# Microcontroller_CC1350.net
KiCad netlist of a schematic drawn in Altium Designer
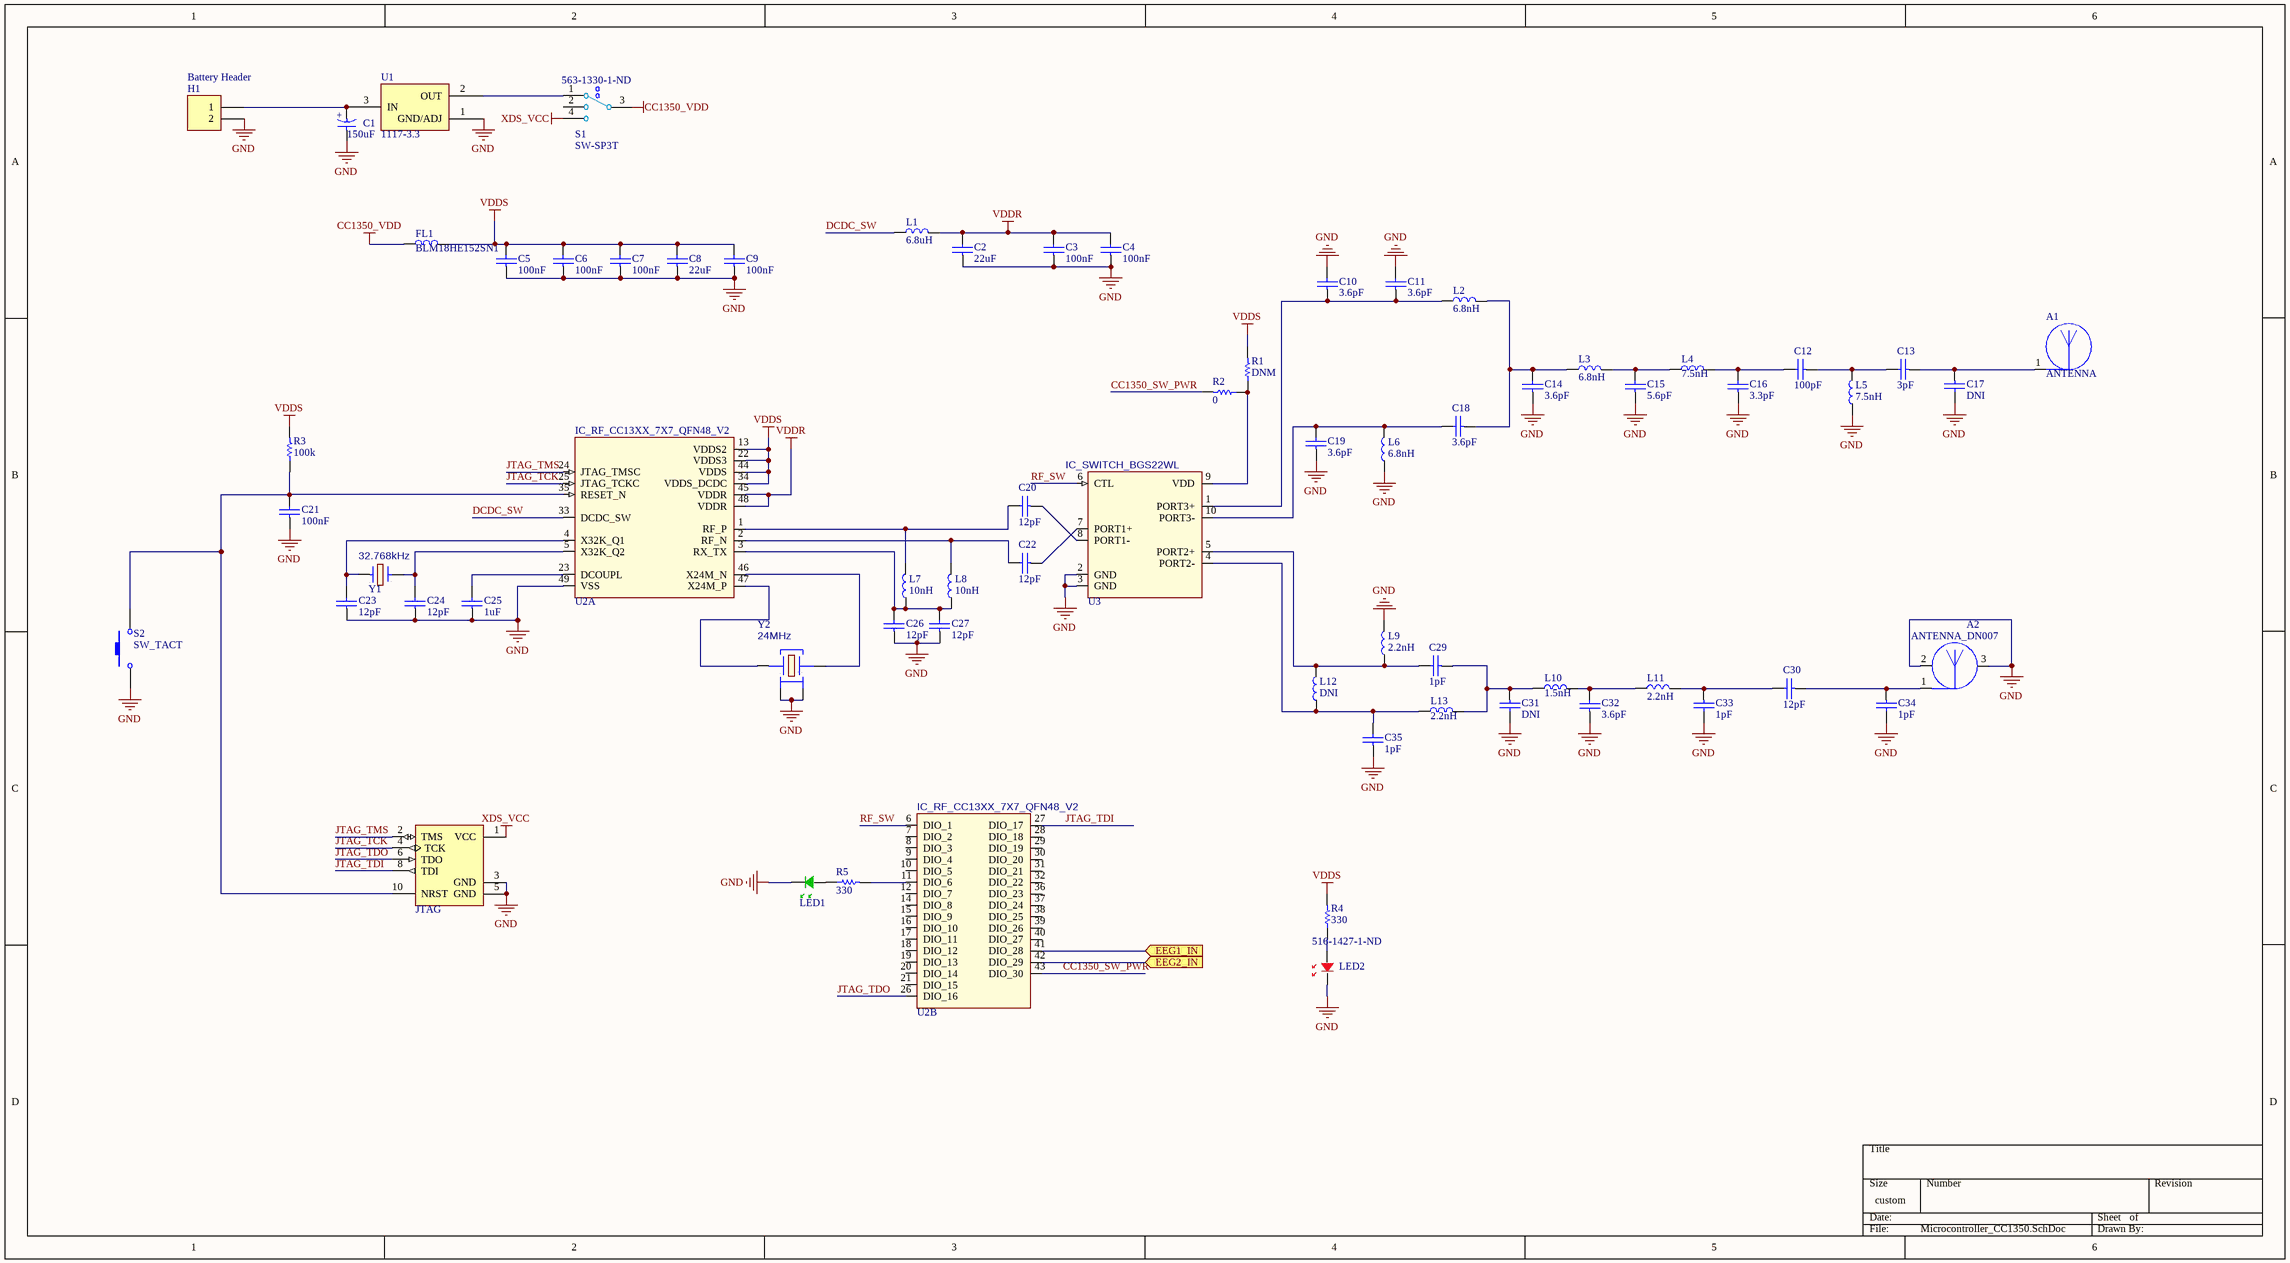
[diagram p0: Microcontroller_CC1350.SchDoc]

(export (version "E")
  (design (tool "Eeschema 10.0.6"))
  (components
    (comp (ref "A1")
      (value "ANTENNA")
      (footprint "Sub-1GHz-Antenna")
      (fields (field (name "DESIGNED BY") "Pawel Kwaskiewicz"))
      (libsource (lib "Biosense_Altium_Library") (part "ANTENNA"))
    )
    (comp (ref "A2")
      (value "ANTENNA_DN007")
      (footprint "Inverted_F_Antenna")
      (fields (field (name "DESIGNED BY") "Artur Bielinski"))
      (libsource (lib "Biosense_Altium_Library") (part "ANTENNA_DN007"))
    )
    (comp (ref "C1")
      (value "150uF")
      (footprint "2312 [IMP] Polar")
      (description "Capacitor")
      (libsource (lib "Biosense_Altium_Library") (part "Cap_E"))
    )
    (comp (ref "C2")
      (value "22uF")
      (footprint "0603[IMP]")
      (fields (field (name "VOLTAGE") "CMAX"))
      (libsource (lib "Biosense_Altium_Library") (part "CAPACITOR"))
    )
    (comp (ref "C3")
      (value "100nF")
      (footprint "0402[IMP]")
      (fields (field (name "VOLTAGE") "CMAX"))
      (libsource (lib "Biosense_Altium_Library") (part "CAPACITOR"))
    )
    (comp (ref "C4")
      (value "100nF")
      (footprint "0402[IMP]")
      (fields (field (name "VOLTAGE") "CMAX"))
      (libsource (lib "Biosense_Altium_Library") (part "CAPACITOR"))
    )
    (comp (ref "C5")
      (value "100nF")
      (footprint "0402[IMP]")
      (fields (field (name "VOLTAGE") "CMAX"))
      (libsource (lib "Biosense_Altium_Library") (part "CAPACITOR"))
    )
    (comp (ref "C6")
      (value "100nF")
      (footprint "0402[IMP]")
      (fields (field (name "VOLTAGE") "CMAX"))
      (libsource (lib "Biosense_Altium_Library") (part "CAPACITOR"))
    )
    (comp (ref "C7")
      (value "100nF")
      (footprint "0402[IMP]")
      (fields (field (name "VOLTAGE") "CMAX"))
      (libsource (lib "Biosense_Altium_Library") (part "CAPACITOR"))
    )
    (comp (ref "C8")
      (value "22uF")
      (footprint "0603[IMP]")
      (fields (field (name "VOLTAGE") "CMAX"))
      (libsource (lib "Biosense_Altium_Library") (part "CAPACITOR"))
    )
    (comp (ref "C9")
      (value "100nF")
      (footprint "0402[IMP]")
      (fields (field (name "VOLTAGE") "CMAX"))
      (libsource (lib "Biosense_Altium_Library") (part "CAPACITOR"))
    )
    (comp (ref "C10")
      (value "3.6pF")
      (footprint "0402[IMP]")
      (fields (field (name "VOLTAGE") "CMAX"))
      (libsource (lib "Biosense_Altium_Library") (part "CAPACITOR"))
    )
    (comp (ref "C11")
      (value "3.6pF")
      (footprint "0402[IMP]")
      (fields (field (name "VOLTAGE") "CMAX"))
      (libsource (lib "Biosense_Altium_Library") (part "CAPACITOR"))
    )
    (comp (ref "C12")
      (value "100pF")
      (footprint "0402[IMP]")
      (fields (field (name "VOLTAGE") "CMAX"))
      (libsource (lib "Biosense_Altium_Library") (part "CAPACITOR"))
    )
    (comp (ref "C13")
      (value "3pF")
      (footprint "0402[IMP]")
      (fields (field (name "VOLTAGE") "CMAX"))
      (libsource (lib "Biosense_Altium_Library") (part "CAPACITOR"))
    )
    (comp (ref "C14")
      (value "3.6pF")
      (footprint "0402[IMP]")
      (fields (field (name "VOLTAGE") "CMAX"))
      (libsource (lib "Biosense_Altium_Library") (part "CAPACITOR"))
    )
    (comp (ref "C15")
      (value "5.6pF")
      (footprint "0402[IMP]")
      (fields (field (name "VOLTAGE") "CMAX"))
      (libsource (lib "Biosense_Altium_Library") (part "CAPACITOR"))
    )
    (comp (ref "C16")
      (value "3.3pF")
      (footprint "0402[IMP]")
      (fields (field (name "VOLTAGE") "CMAX"))
      (libsource (lib "Biosense_Altium_Library") (part "CAPACITOR"))
    )
    (comp (ref "C17")
      (value "DNI")
      (footprint "0402[IMP]")
      (fields (field (name "VOLTAGE") "CMAX"))
      (libsource (lib "Biosense_Altium_Library") (part "CAPACITOR"))
    )
    (comp (ref "C18")
      (value "3.6pF")
      (footprint "0402[IMP]")
      (fields (field (name "VOLTAGE") "CMAX"))
      (libsource (lib "Biosense_Altium_Library") (part "CAPACITOR"))
    )
    (comp (ref "C19")
      (value "3.6pF")
      (footprint "0402[IMP]")
      (fields (field (name "VOLTAGE") "CMAX"))
      (libsource (lib "Biosense_Altium_Library") (part "CAPACITOR"))
    )
    (comp (ref "C20")
      (value "12pF")
      (footprint "0402[IMP]")
      (fields (field (name "VOLTAGE") "CMAX"))
      (libsource (lib "Biosense_Altium_Library") (part "CAPACITOR"))
    )
    (comp (ref "C21")
      (value "100nF")
      (footprint "0402[IMP]")
      (fields (field (name "VOLTAGE") "CMAX"))
      (libsource (lib "Biosense_Altium_Library") (part "CAPACITOR"))
    )
    (comp (ref "C22")
      (value "12pF")
      (footprint "0402[IMP]")
      (fields (field (name "VOLTAGE") "CMAX"))
      (libsource (lib "Biosense_Altium_Library") (part "CAPACITOR"))
    )
    (comp (ref "C23")
      (value "12pF")
      (footprint "0402[IMP]")
      (fields (field (name "VOLTAGE") "CMAX"))
      (libsource (lib "Biosense_Altium_Library") (part "CAPACITOR"))
    )
    (comp (ref "C24")
      (value "12pF")
      (footprint "0402[IMP]")
      (fields (field (name "VOLTAGE") "CMAX"))
      (libsource (lib "Biosense_Altium_Library") (part "CAPACITOR"))
    )
    (comp (ref "C25")
      (value "1uF")
      (footprint "0402[IMP]")
      (fields (field (name "VOLTAGE") "CMAX"))
      (libsource (lib "Biosense_Altium_Library") (part "CAPACITOR"))
    )
    (comp (ref "C26")
      (value "12pF")
      (footprint "0402[IMP]")
      (fields (field (name "VOLTAGE") "CMAX"))
      (libsource (lib "Biosense_Altium_Library") (part "CAPACITOR"))
    )
    (comp (ref "C27")
      (value "12pF")
      (footprint "0402[IMP]")
      (fields (field (name "VOLTAGE") "CMAX"))
      (libsource (lib "Biosense_Altium_Library") (part "CAPACITOR"))
    )
    (comp (ref "C29")
      (value "1pF")
      (footprint "0402[IMP]")
      (fields (field (name "VOLTAGE") "CMAX"))
      (libsource (lib "Biosense_Altium_Library") (part "CAPACITOR"))
    )
    (comp (ref "C30")
      (value "12pF")
      (footprint "0402[IMP]")
      (fields (field (name "VOLTAGE") "CMAX"))
      (libsource (lib "Biosense_Altium_Library") (part "CAPACITOR"))
    )
    (comp (ref "C31")
      (value "DNI")
      (footprint "0402[IMP]")
      (fields (field (name "VOLTAGE") "CMAX"))
      (libsource (lib "Biosense_Altium_Library") (part "CAPACITOR"))
    )
    (comp (ref "C32")
      (value "3.6pF")
      (footprint "0402[IMP]")
      (fields (field (name "VOLTAGE") "CMAX"))
      (libsource (lib "Biosense_Altium_Library") (part "CAPACITOR"))
    )
    (comp (ref "C33")
      (value "1pF")
      (footprint "0402[IMP]")
      (fields (field (name "VOLTAGE") "CMAX"))
      (libsource (lib "Biosense_Altium_Library") (part "CAPACITOR"))
    )
    (comp (ref "C34")
      (value "1pF")
      (footprint "0402[IMP]")
      (fields (field (name "VOLTAGE") "CMAX"))
      (libsource (lib "Biosense_Altium_Library") (part "CAPACITOR"))
    )
    (comp (ref "C35")
      (value "1pF")
      (footprint "0402[IMP]")
      (fields (field (name "VOLTAGE") "CMAX"))
      (libsource (lib "Biosense_Altium_Library") (part "CAPACITOR"))
    )
    (comp (ref "FL1")
      (value "BLM18HE152SN1")
      (footprint "0603[IMP]")
      (libsource (lib "Biosense_Altium_Library") (part "INDUCTOR"))
    )
    (comp (ref "H1")
      (value "Battery Header")
      (footprint "S2B-PH-SM4-TB")
      (libsource (lib "Biosense_Altium_Library") (part "Header 2"))
    )
    (comp (ref "H2")
      (value "JTAG")
      (footprint "HDR-2*5-0.05_Without_Through_Hole")
      (description "USB JTAG Programmer")
      (libsource (lib "Biosense_Altium_Library") (part "JTAG-ARM"))
    )
    (comp (ref "L1")
      (value "6.8uH")
      (footprint "0805[IMP]")
      (libsource (lib "Biosense_Altium_Library") (part "INDUCTOR"))
    )
    (comp (ref "L2")
      (value "6.8nH")
      (footprint "0402[IMP]")
      (libsource (lib "Biosense_Altium_Library") (part "INDUCTOR"))
    )
    (comp (ref "L3")
      (value "6.8nH")
      (footprint "0402[IMP]")
      (libsource (lib "Biosense_Altium_Library") (part "INDUCTOR"))
    )
    (comp (ref "L4")
      (value "7.5nH")
      (footprint "0402[IMP]")
      (libsource (lib "Biosense_Altium_Library") (part "INDUCTOR"))
    )
    (comp (ref "L5")
      (value "7.5nH")
      (footprint "0402[IMP]")
      (libsource (lib "Biosense_Altium_Library") (part "INDUCTOR"))
    )
    (comp (ref "L6")
      (value "6.8nH")
      (footprint "0402[IMP]")
      (libsource (lib "Biosense_Altium_Library") (part "INDUCTOR"))
    )
    (comp (ref "L7")
      (value "10nH")
      (footprint "0402[IMP]")
      (libsource (lib "Biosense_Altium_Library") (part "INDUCTOR"))
    )
    (comp (ref "L8")
      (value "10nH")
      (footprint "0402[IMP]")
      (libsource (lib "Biosense_Altium_Library") (part "INDUCTOR"))
    )
    (comp (ref "L9")
      (value "2.2nH")
      (footprint "0402[IMP]")
      (libsource (lib "Biosense_Altium_Library") (part "INDUCTOR"))
    )
    (comp (ref "L10")
      (value "1.5nH")
      (footprint "0402[IMP]")
      (libsource (lib "Biosense_Altium_Library") (part "INDUCTOR"))
    )
    (comp (ref "L11")
      (value "2.2nH")
      (footprint "0402[IMP]")
      (libsource (lib "Biosense_Altium_Library") (part "INDUCTOR"))
    )
    (comp (ref "L12")
      (value "DNI")
      (footprint "0402[IMP]")
      (libsource (lib "Biosense_Altium_Library") (part "INDUCTOR"))
    )
    (comp (ref "L13")
      (value "2.2nH")
      (footprint "0402[IMP]")
      (libsource (lib "Biosense_Altium_Library") (part "INDUCTOR"))
    )
    (comp (ref "LED1")
      (value "LEDG")
      (footprint "0805[IMP] - POLAR")
      (description "LED")
      (libsource (lib "Biosense_Altium_Library") (part "LED_G"))
    )
    (comp (ref "LED2")
      (value "LEDR")
      (footprint "0805[IMP] - POLAR")
      (description "LED")
      (fields (field (name "SUPPLIER PART NUMBER 1") "516-1427-1-ND"))
      (libsource (lib "Biosense_Altium_Library") (part "LED_R"))
    )
    (comp (ref "R1")
      (value "DNM")
      (footprint "0402[IMP]")
      (libsource (lib "Biosense_Altium_Library") (part "RESISTOR"))
    )
    (comp (ref "R2")
      (value "0")
      (footprint "0402[IMP]")
      (libsource (lib "Biosense_Altium_Library") (part "RESISTOR"))
    )
    (comp (ref "R3")
      (value "100k")
      (footprint "0402[IMP]")
      (libsource (lib "Biosense_Altium_Library") (part "RESISTOR"))
    )
    (comp (ref "R4")
      (value "330")
      (footprint "0402[IMP]")
      (libsource (lib "Biosense_Altium_Library") (part "RESISTOR"))
    )
    (comp (ref "R5")
      (value "330")
      (footprint "0402[IMP]")
      (libsource (lib "Biosense_Altium_Library") (part "RESISTOR"))
    )
    (comp (ref "S1")
      (value "SW-SP3T")
      (footprint "CL-SB-13B")
      (fields (field (name "SUPPLIER PART NUMBER 1") "563-1330-1-ND"))
      (libsource (lib "Biosense_Altium_Library") (part "SW-SP3T"))
    )
    (comp (ref "S2")
      (value "SW_TACT")
      (footprint "PTS645SH50SMTR92_LFS")
      (description "Tactile switch")
      (libsource (lib "Biosense_Altium_Library") (part "SW_TACT"))
    )
    (comp (ref "U1")
      (value "1117-3.3")
      (footprint "SOT-223")
      (description "3.3V Voltage Regulator")
      (libsource (lib "Biosense_Altium_Library") (part "1117-3.3V"))
    )
    (comp (ref "U2")
      (value "IC_RF_CC13XX_7X7_QFN48_V2")
      (footprint "RGZ(S-PVQFN-N48) - duplicate")
      (fields (field (name "DESIGNED_BY") "Artur Bielinski"))
      (libsource (lib "Biosense_Altium_Library") (part "IC_RF_CC13XX_7X7_QFN48_V2"))
    )
    (comp (ref "U3")
      (value "IC_SWITCH_BGS22WL")
      (footprint "TSLP-10-1")
      (fields (field (name "DESIGNED_BY") "Artur Bielinski"))
      (libsource (lib "Biosense_Altium_Library") (part "IC_SWITCH_XMSSJE3G0PA-00"))
    )
    (comp (ref "Y1")
      (value "32.768kHz")
      (footprint "FC-135")
      (libsource (lib "Biosense_Altium_Library") (part "CRYSTAL"))
    )
    (comp (ref "Y2")
      (value "24MHz")
      (footprint "TSX-3225")
      (libsource (lib "Biosense_Altium_Library") (part "XTAL_4PIN_S"))
    )
  )
  (nets
    (net (code "1") (name "/CC1350_SW_PWR") (class "Default")
      (node (ref "R2") (pin "2") (pinfunction "2_2") (pintype "passive"))
      (node (ref "U2") (pin "43") (pinfunction "DIO_30_43") (pintype "bidirectional"))
    )
    (net (code "2") (name "/DCDC_SW") (class "Default")
      (node (ref "L1") (pin "1") (pinfunction "1_1") (pintype "passive"))
      (node (ref "U2") (pin "33") (pinfunction "DCDC_SW_33") (pintype "power_in"))
    )
    (net (code "3") (name "/EEG1_IN") (class "Default")
      (node (ref "U2") (pin "41") (pinfunction "DIO_28_41") (pintype "bidirectional"))
    )
    (net (code "4") (name "/EEG2_IN") (class "Default")
      (node (ref "U2") (pin "42") (pinfunction "DIO_29_42") (pintype "bidirectional"))
    )
    (net (code "5") (name "/JTAG_TCK") (class "Default")
      (node (ref "H2") (pin "4") (pinfunction "TCK_4") (pintype "output"))
      (node (ref "U2") (pin "25") (pinfunction "JTAG_TCKC_25") (pintype "input"))
    )
    (net (code "6") (name "/JTAG_TDI") (class "Default")
      (node (ref "H2") (pin "8") (pinfunction "TDI_8") (pintype "output"))
      (node (ref "U2") (pin "27") (pinfunction "DIO_17_27") (pintype "bidirectional"))
    )
    (net (code "7") (name "/JTAG_TDO") (class "Default")
      (node (ref "H2") (pin "6") (pinfunction "TDO_6") (pintype "input"))
      (node (ref "U2") (pin "26") (pinfunction "DIO_16_26") (pintype "bidirectional"))
    )
    (net (code "8") (name "/JTAG_TMS") (class "Default")
      (node (ref "H2") (pin "2") (pinfunction "TMS_2") (pintype "bidirectional"))
      (node (ref "U2") (pin "24") (pinfunction "JTAG_TMSC_24") (pintype "input"))
    )
    (net (code "9") (name "/RF_SW") (class "Default")
      (node (ref "U2") (pin "6") (pinfunction "DIO_1_6") (pintype "bidirectional"))
      (node (ref "U3") (pin "6") (pinfunction "CTL_6") (pintype "input"))
    )
    (net (code "10") (name "CC1350_VDD") (class "Default")
      (node (ref "FL1") (pin "1") (pinfunction "1_1") (pintype "passive"))
      (node (ref "S1") (pin "3") (pinfunction "3_3") (pintype "passive"))
    )
    (net (code "11") (name "GND") (class "Default")
      (node (ref "A2") (pin "2") (pinfunction "GND_2_2") (pintype "passive"))
      (node (ref "A2") (pin "3") (pinfunction "GND_3_3") (pintype "passive"))
      (node (ref "C1") (pin "1") (pinfunction "1_1") (pintype "passive"))
      (node (ref "C10") (pin "1") (pinfunction "1_1") (pintype "passive"))
      (node (ref "C11") (pin "1") (pinfunction "1_1") (pintype "passive"))
      (node (ref "C14") (pin "2") (pinfunction "2_2") (pintype "passive"))
      (node (ref "C15") (pin "2") (pinfunction "2_2") (pintype "passive"))
      (node (ref "C16") (pin "2") (pinfunction "2_2") (pintype "passive"))
      (node (ref "C17") (pin "1") (pinfunction "1_1") (pintype "passive"))
      (node (ref "C19") (pin "2") (pinfunction "2_2") (pintype "passive"))
      (node (ref "C2") (pin "2") (pinfunction "2_2") (pintype "passive"))
      (node (ref "C21") (pin "2") (pinfunction "2_2") (pintype "passive"))
      (node (ref "C23") (pin "2") (pinfunction "2_2") (pintype "passive"))
      (node (ref "C24") (pin "2") (pinfunction "2_2") (pintype "passive"))
      (node (ref "C25") (pin "2") (pinfunction "2_2") (pintype "passive"))
      (node (ref "C26") (pin "2") (pinfunction "2_2") (pintype "passive"))
      (node (ref "C27") (pin "2") (pinfunction "2_2") (pintype "passive"))
      (node (ref "C3") (pin "2") (pinfunction "2_2") (pintype "passive"))
      (node (ref "C31") (pin "1") (pinfunction "1_1") (pintype "passive"))
      (node (ref "C32") (pin "2") (pinfunction "2_2") (pintype "passive"))
      (node (ref "C33") (pin "1") (pinfunction "1_1") (pintype "passive"))
      (node (ref "C34") (pin "1") (pinfunction "1_1") (pintype "passive"))
      (node (ref "C35") (pin "2") (pinfunction "2_2") (pintype "passive"))
      (node (ref "C4") (pin "2") (pinfunction "2_2") (pintype "passive"))
      (node (ref "C5") (pin "2") (pinfunction "2_2") (pintype "passive"))
      (node (ref "C6") (pin "2") (pinfunction "2_2") (pintype "passive"))
      (node (ref "C7") (pin "2") (pinfunction "2_2") (pintype "passive"))
      (node (ref "C8") (pin "2") (pinfunction "2_2") (pintype "passive"))
      (node (ref "C9") (pin "2") (pinfunction "2_2") (pintype "passive"))
      (node (ref "H1") (pin "2") (pinfunction "2_2") (pintype "passive"))
      (node (ref "H2") (pin "3") (pinfunction "GND_3") (pintype "power_in"))
      (node (ref "H2") (pin "5") (pinfunction "GND_5") (pintype "power_in"))
      (node (ref "L5") (pin "1") (pinfunction "1_1") (pintype "passive"))
      (node (ref "L6") (pin "1") (pinfunction "1_1") (pintype "passive"))
      (node (ref "L9") (pin "2") (pinfunction "2_2") (pintype "passive"))
      (node (ref "LED1") (pin "2") (pinfunction "K_2") (pintype "passive"))
      (node (ref "LED2") (pin "2") (pinfunction "K_2") (pintype "passive"))
      (node (ref "S2") (pin "1") (pinfunction "1_1") (pintype "passive"))
      (node (ref "U1") (pin "1") (pinfunction "GND/ADJ_1") (pintype "passive"))
      (node (ref "U2") (pin "49") (pinfunction "VSS_49") (pintype "power_in"))
      (node (ref "U3") (pin "2") (pinfunction "GND_2") (pintype "power_in"))
      (node (ref "U3") (pin "3") (pinfunction "GND_3") (pintype "power_in"))
      (node (ref "Y2") (pin "2") (pinfunction "2_2") (pintype "power_in"))
      (node (ref "Y2") (pin "4") (pinfunction "4_4") (pintype "power_in"))
    )
    (net (code "12") (name "Net-(A1-FEED{slash}GND_1)") (class "Default")
      (node (ref "A1") (pin "1") (pinfunction "FEED/GND_1_1") (pintype "passive"))
      (node (ref "C13") (pin "2") (pinfunction "2_2") (pintype "passive"))
      (node (ref "C17") (pin "2") (pinfunction "2_2") (pintype "passive"))
    )
    (net (code "13") (name "Net-(A2-FEED_1)") (class "Default")
      (node (ref "A2") (pin "1") (pinfunction "FEED_1_1") (pintype "passive"))
      (node (ref "C30") (pin "2") (pinfunction "2_2") (pintype "passive"))
      (node (ref "C34") (pin "2") (pinfunction "2_2") (pintype "passive"))
    )
    (net (code "14") (name "Net-(C12-Pad1)") (class "Default")
      (node (ref "C12") (pin "1") (pinfunction "1_1") (pintype "passive"))
      (node (ref "C16") (pin "1") (pinfunction "1_1") (pintype "passive"))
      (node (ref "L4") (pin "2") (pinfunction "2_2") (pintype "passive"))
    )
    (net (code "15") (name "Net-(C12-Pad2)") (class "Default")
      (node (ref "C12") (pin "2") (pinfunction "2_2") (pintype "passive"))
      (node (ref "C13") (pin "1") (pinfunction "1_1") (pintype "passive"))
      (node (ref "L5") (pin "2") (pinfunction "2_2") (pintype "passive"))
    )
    (net (code "16") (name "Net-(C14-Pad1)") (class "Default")
      (node (ref "C14") (pin "1") (pinfunction "1_1") (pintype "passive"))
      (node (ref "C18") (pin "2") (pinfunction "2_2") (pintype "passive"))
      (node (ref "L2") (pin "2") (pinfunction "2_2") (pintype "passive"))
      (node (ref "L3") (pin "1") (pinfunction "1_1") (pintype "passive"))
    )
    (net (code "17") (name "Net-(C15-Pad1)") (class "Default")
      (node (ref "C15") (pin "1") (pinfunction "1_1") (pintype "passive"))
      (node (ref "L3") (pin "2") (pinfunction "2_2") (pintype "passive"))
      (node (ref "L4") (pin "1") (pinfunction "1_1") (pintype "passive"))
    )
    (net (code "18") (name "Net-(C29-Pad2)") (class "Default")
      (node (ref "C29") (pin "2") (pinfunction "2_2") (pintype "passive"))
      (node (ref "C31") (pin "2") (pinfunction "2_2") (pintype "passive"))
      (node (ref "L10") (pin "1") (pinfunction "1_1") (pintype "passive"))
      (node (ref "L13") (pin "2") (pinfunction "2_2") (pintype "passive"))
    )
    (net (code "19") (name "Net-(C30-Pad1)") (class "Default")
      (node (ref "C30") (pin "1") (pinfunction "1_1") (pintype "passive"))
      (node (ref "C33") (pin "2") (pinfunction "2_2") (pintype "passive"))
      (node (ref "L11") (pin "2") (pinfunction "2_2") (pintype "passive"))
    )
    (net (code "20") (name "Net-(C32-Pad1)") (class "Default")
      (node (ref "C32") (pin "1") (pinfunction "1_1") (pintype "passive"))
      (node (ref "L10") (pin "2") (pinfunction "2_2") (pintype "passive"))
      (node (ref "L11") (pin "1") (pinfunction "1_1") (pintype "passive"))
    )
    (net (code "21") (name "Net-(H2-NRST)") (class "Default")
      (node (ref "C21") (pin "1") (pinfunction "1_1") (pintype "passive"))
      (node (ref "H2") (pin "10") (pinfunction "NRST_10") (pintype "passive"))
      (node (ref "R3") (pin "1") (pinfunction "1_1") (pintype "passive"))
      (node (ref "S2") (pin "2") (pinfunction "2_2") (pintype "passive"))
      (node (ref "U2") (pin "35") (pinfunction "RESET_N_35") (pintype "input"))
    )
    (net (code "22") (name "Net-(LED1-A)") (class "Default")
      (node (ref "LED1") (pin "1") (pinfunction "A_1") (pintype "passive"))
      (node (ref "R5") (pin "1") (pinfunction "1_1") (pintype "passive"))
    )
    (net (code "23") (name "Net-(LED2-A)") (class "Default")
      (node (ref "LED2") (pin "1") (pinfunction "A_1") (pintype "passive"))
      (node (ref "R4") (pin "1") (pinfunction "1_1") (pintype "passive"))
    )
    (net (code "24") (name "Net-(U1-IN)") (class "Default")
      (node (ref "C1") (pin "2") (pinfunction "2_2") (pintype "passive"))
      (node (ref "H1") (pin "1") (pinfunction "1_1") (pintype "passive"))
      (node (ref "U1") (pin "3") (pinfunction "IN_3") (pintype "passive"))
    )
    (net (code "25") (name "Net-(U1-OUT)") (class "Default")
      (node (ref "S1") (pin "1") (pinfunction "1_1") (pintype "passive"))
      (node (ref "U1") (pin "2") (pinfunction "OUT_2") (pintype "passive"))
    )
    (net (code "26") (name "Net-(U2A-DCOUPL)") (class "Default")
      (node (ref "C25") (pin "1") (pinfunction "1_1") (pintype "passive"))
      (node (ref "U2") (pin "23") (pinfunction "DCOUPL_23") (pintype "passive"))
    )
    (net (code "27") (name "Net-(U2A-RF_N)") (class "Default")
      (node (ref "C22") (pin "1") (pinfunction "1_1") (pintype "passive"))
      (node (ref "L8") (pin "2") (pinfunction "2_2") (pintype "passive"))
      (node (ref "U2") (pin "2") (pinfunction "RF_N_2") (pintype "passive"))
    )
    (net (code "28") (name "Net-(U2A-RF_P)") (class "Default")
      (node (ref "C20") (pin "1") (pinfunction "1_1") (pintype "passive"))
      (node (ref "L7") (pin "2") (pinfunction "2_2") (pintype "passive"))
      (node (ref "U2") (pin "1") (pinfunction "RF_P_1") (pintype "passive"))
    )
    (net (code "29") (name "Net-(U2A-RX_TX)") (class "Default")
      (node (ref "C26") (pin "1") (pinfunction "1_1") (pintype "passive"))
      (node (ref "C27") (pin "1") (pinfunction "1_1") (pintype "passive"))
      (node (ref "L7") (pin "1") (pinfunction "1_1") (pintype "passive"))
      (node (ref "L8") (pin "1") (pinfunction "1_1") (pintype "passive"))
      (node (ref "U2") (pin "3") (pinfunction "RX_TX_3") (pintype "bidirectional"))
    )
    (net (code "30") (name "Net-(U2A-X24M_N)") (class "Default")
      (node (ref "U2") (pin "46") (pinfunction "X24M_N_46") (pintype "passive"))
      (node (ref "Y2") (pin "3") (pinfunction "3_3") (pintype "passive"))
    )
    (net (code "31") (name "Net-(U2A-X24M_P)") (class "Default")
      (node (ref "U2") (pin "47") (pinfunction "X24M_P_47") (pintype "passive"))
      (node (ref "Y2") (pin "1") (pinfunction "1_1") (pintype "passive"))
    )
    (net (code "32") (name "Net-(U2A-X32K_Q1)") (class "Default")
      (node (ref "C23") (pin "1") (pinfunction "1_1") (pintype "passive"))
      (node (ref "U2") (pin "4") (pinfunction "X32K_Q1_4") (pintype "passive"))
      (node (ref "Y1") (pin "1") (pinfunction "1_1") (pintype "passive"))
    )
    (net (code "33") (name "Net-(U2A-X32K_Q2)") (class "Default")
      (node (ref "C24") (pin "1") (pinfunction "1_1") (pintype "passive"))
      (node (ref "U2") (pin "5") (pinfunction "X32K_Q2_5") (pintype "passive"))
      (node (ref "Y1") (pin "2") (pinfunction "2_2") (pintype "passive"))
    )
    (net (code "34") (name "Net-(U2B-DIO_6)") (class "Default")
      (node (ref "R5") (pin "2") (pinfunction "2_2") (pintype "passive"))
      (node (ref "U2") (pin "11") (pinfunction "DIO_6_11") (pintype "bidirectional"))
    )
    (net (code "35") (name "Net-(U3-PORT1+)") (class "Default")
      (node (ref "C22") (pin "2") (pinfunction "2_2") (pintype "passive"))
      (node (ref "U3") (pin "7") (pinfunction "PORT1+_7") (pintype "passive"))
    )
    (net (code "36") (name "Net-(U3-PORT1-)") (class "Default")
      (node (ref "C20") (pin "2") (pinfunction "2_2") (pintype "passive"))
      (node (ref "U3") (pin "8") (pinfunction "PORT1-_8") (pintype "passive"))
    )
    (net (code "37") (name "Net-(U3-PORT2+)") (class "Default")
      (node (ref "C29") (pin "1") (pinfunction "1_1") (pintype "passive"))
      (node (ref "L12") (pin "2") (pinfunction "2_2") (pintype "passive"))
      (node (ref "L9") (pin "1") (pinfunction "1_1") (pintype "passive"))
      (node (ref "U3") (pin "5") (pinfunction "PORT2+_5") (pintype "passive"))
    )
    (net (code "38") (name "Net-(U3-PORT2-)") (class "Default")
      (node (ref "C35") (pin "1") (pinfunction "1_1") (pintype "passive"))
      (node (ref "L12") (pin "1") (pinfunction "1_1") (pintype "passive"))
      (node (ref "L13") (pin "1") (pinfunction "1_1") (pintype "passive"))
      (node (ref "U3") (pin "4") (pinfunction "PORT2-_4") (pintype "passive"))
    )
    (net (code "39") (name "Net-(U3-PORT3+)") (class "Default")
      (node (ref "C10") (pin "2") (pinfunction "2_2") (pintype "passive"))
      (node (ref "C11") (pin "2") (pinfunction "2_2") (pintype "passive"))
      (node (ref "L2") (pin "1") (pinfunction "1_1") (pintype "passive"))
      (node (ref "U3") (pin "1") (pinfunction "PORT3+_1") (pintype "passive"))
    )
    (net (code "40") (name "Net-(U3-PORT3-)") (class "Default")
      (node (ref "C18") (pin "1") (pinfunction "1_1") (pintype "passive"))
      (node (ref "C19") (pin "1") (pinfunction "1_1") (pintype "passive"))
      (node (ref "L6") (pin "2") (pinfunction "2_2") (pintype "passive"))
      (node (ref "U3") (pin "10") (pinfunction "PORT3-_10") (pintype "passive"))
    )
    (net (code "41") (name "Net-(U3-VDD)") (class "Default")
      (node (ref "R1") (pin "1") (pinfunction "1_1") (pintype "passive"))
      (node (ref "R2") (pin "1") (pinfunction "1_1") (pintype "passive"))
      (node (ref "U3") (pin "9") (pinfunction "VDD_9") (pintype "power_in"))
    )
    (net (code "42") (name "VDDR") (class "Default")
      (node (ref "C2") (pin "1") (pinfunction "1_1") (pintype "passive"))
      (node (ref "C3") (pin "1") (pinfunction "1_1") (pintype "passive"))
      (node (ref "C4") (pin "1") (pinfunction "1_1") (pintype "passive"))
      (node (ref "L1") (pin "2") (pinfunction "2_2") (pintype "passive"))
      (node (ref "U2") (pin "45") (pinfunction "VDDR_45") (pintype "power_in"))
      (node (ref "U2") (pin "48") (pinfunction "VDDR_48") (pintype "power_in"))
    )
    (net (code "43") (name "VDDS") (class "Default")
      (node (ref "C5") (pin "1") (pinfunction "1_1") (pintype "passive"))
      (node (ref "C6") (pin "1") (pinfunction "1_1") (pintype "passive"))
      (node (ref "C7") (pin "1") (pinfunction "1_1") (pintype "passive"))
      (node (ref "C8") (pin "1") (pinfunction "1_1") (pintype "passive"))
      (node (ref "C9") (pin "1") (pinfunction "1_1") (pintype "passive"))
      (node (ref "FL1") (pin "2") (pinfunction "2_2") (pintype "passive"))
      (node (ref "R1") (pin "2") (pinfunction "2_2") (pintype "passive"))
      (node (ref "R3") (pin "2") (pinfunction "2_2") (pintype "passive"))
      (node (ref "R4") (pin "2") (pinfunction "2_2") (pintype "passive"))
      (node (ref "U2") (pin "13") (pinfunction "VDDS2_13") (pintype "power_in"))
      (node (ref "U2") (pin "22") (pinfunction "VDDS3_22") (pintype "power_in"))
      (node (ref "U2") (pin "34") (pinfunction "VDDS_DCDC_34") (pintype "power_in"))
      (node (ref "U2") (pin "44") (pinfunction "VDDS_44") (pintype "power_in"))
    )
    (net (code "44") (name "XDS_VCC") (class "Default")
      (node (ref "H2") (pin "1") (pinfunction "VCC_1") (pintype "power_in"))
      (node (ref "S1") (pin "4") (pinfunction "4_4") (pintype "passive"))
    )
    (net (code "45") (name "unconnected-(S1-Pad2)") (class "Default")
      (node (ref "S1") (pin "2") (pinfunction "2_2") (pintype "passive"))
    )
    (net (code "46") (name "unconnected-(U2B-DIO_2-Pad7)") (class "Default")
      (node (ref "U2") (pin "7") (pinfunction "DIO_2_7") (pintype "bidirectional"))
    )
    (net (code "47") (name "unconnected-(U2B-DIO_3-Pad8)") (class "Default")
      (node (ref "U2") (pin "8") (pinfunction "DIO_3_8") (pintype "bidirectional"))
    )
    (net (code "48") (name "unconnected-(U2B-DIO_4-Pad9)") (class "Default")
      (node (ref "U2") (pin "9") (pinfunction "DIO_4_9") (pintype "bidirectional"))
    )
    (net (code "49") (name "unconnected-(U2B-DIO_5-Pad10)") (class "Default")
      (node (ref "U2") (pin "10") (pinfunction "DIO_5_10") (pintype "bidirectional"))
    )
    (net (code "50") (name "unconnected-(U2B-DIO_7-Pad12)") (class "Default")
      (node (ref "U2") (pin "12") (pinfunction "DIO_7_12") (pintype "bidirectional"))
    )
    (net (code "51") (name "unconnected-(U2B-DIO_8-Pad14)") (class "Default")
      (node (ref "U2") (pin "14") (pinfunction "DIO_8_14") (pintype "bidirectional"))
    )
    (net (code "52") (name "unconnected-(U2B-DIO_9-Pad15)") (class "Default")
      (node (ref "U2") (pin "15") (pinfunction "DIO_9_15") (pintype "bidirectional"))
    )
    (net (code "53") (name "unconnected-(U2B-DIO_10-Pad16)") (class "Default")
      (node (ref "U2") (pin "16") (pinfunction "DIO_10_16") (pintype "bidirectional"))
    )
    (net (code "54") (name "unconnected-(U2B-DIO_11-Pad17)") (class "Default")
      (node (ref "U2") (pin "17") (pinfunction "DIO_11_17") (pintype "bidirectional"))
    )
    (net (code "55") (name "unconnected-(U2B-DIO_12-Pad18)") (class "Default")
      (node (ref "U2") (pin "18") (pinfunction "DIO_12_18") (pintype "bidirectional"))
    )
    (net (code "56") (name "unconnected-(U2B-DIO_13-Pad19)") (class "Default")
      (node (ref "U2") (pin "19") (pinfunction "DIO_13_19") (pintype "bidirectional"))
    )
    (net (code "57") (name "unconnected-(U2B-DIO_14-Pad20)") (class "Default")
      (node (ref "U2") (pin "20") (pinfunction "DIO_14_20") (pintype "bidirectional"))
    )
    (net (code "58") (name "unconnected-(U2B-DIO_15-Pad21)") (class "Default")
      (node (ref "U2") (pin "21") (pinfunction "DIO_15_21") (pintype "bidirectional"))
    )
    (net (code "59") (name "unconnected-(U2B-DIO_18-Pad28)") (class "Default")
      (node (ref "U2") (pin "28") (pinfunction "DIO_18_28") (pintype "bidirectional"))
    )
    (net (code "60") (name "unconnected-(U2B-DIO_19-Pad29)") (class "Default")
      (node (ref "U2") (pin "29") (pinfunction "DIO_19_29") (pintype "bidirectional"))
    )
    (net (code "61") (name "unconnected-(U2B-DIO_20-Pad30)") (class "Default")
      (node (ref "U2") (pin "30") (pinfunction "DIO_20_30") (pintype "bidirectional"))
    )
    (net (code "62") (name "unconnected-(U2B-DIO_21-Pad31)") (class "Default")
      (node (ref "U2") (pin "31") (pinfunction "DIO_21_31") (pintype "bidirectional"))
    )
    (net (code "63") (name "unconnected-(U2B-DIO_22-Pad32)") (class "Default")
      (node (ref "U2") (pin "32") (pinfunction "DIO_22_32") (pintype "bidirectional"))
    )
    (net (code "64") (name "unconnected-(U2B-DIO_23-Pad36)") (class "Default")
      (node (ref "U2") (pin "36") (pinfunction "DIO_23_36") (pintype "bidirectional"))
    )
    (net (code "65") (name "unconnected-(U2B-DIO_24-Pad37)") (class "Default")
      (node (ref "U2") (pin "37") (pinfunction "DIO_24_37") (pintype "bidirectional"))
    )
    (net (code "66") (name "unconnected-(U2B-DIO_25-Pad38)") (class "Default")
      (node (ref "U2") (pin "38") (pinfunction "DIO_25_38") (pintype "bidirectional"))
    )
    (net (code "67") (name "unconnected-(U2B-DIO_26-Pad39)") (class "Default")
      (node (ref "U2") (pin "39") (pinfunction "DIO_26_39") (pintype "bidirectional"))
    )
    (net (code "68") (name "unconnected-(U2B-DIO_27-Pad40)") (class "Default")
      (node (ref "U2") (pin "40") (pinfunction "DIO_27_40") (pintype "bidirectional"))
    )
  )
)
